# Sheet1.net
KiCad netlist of a schematic drawn in Altium Designer
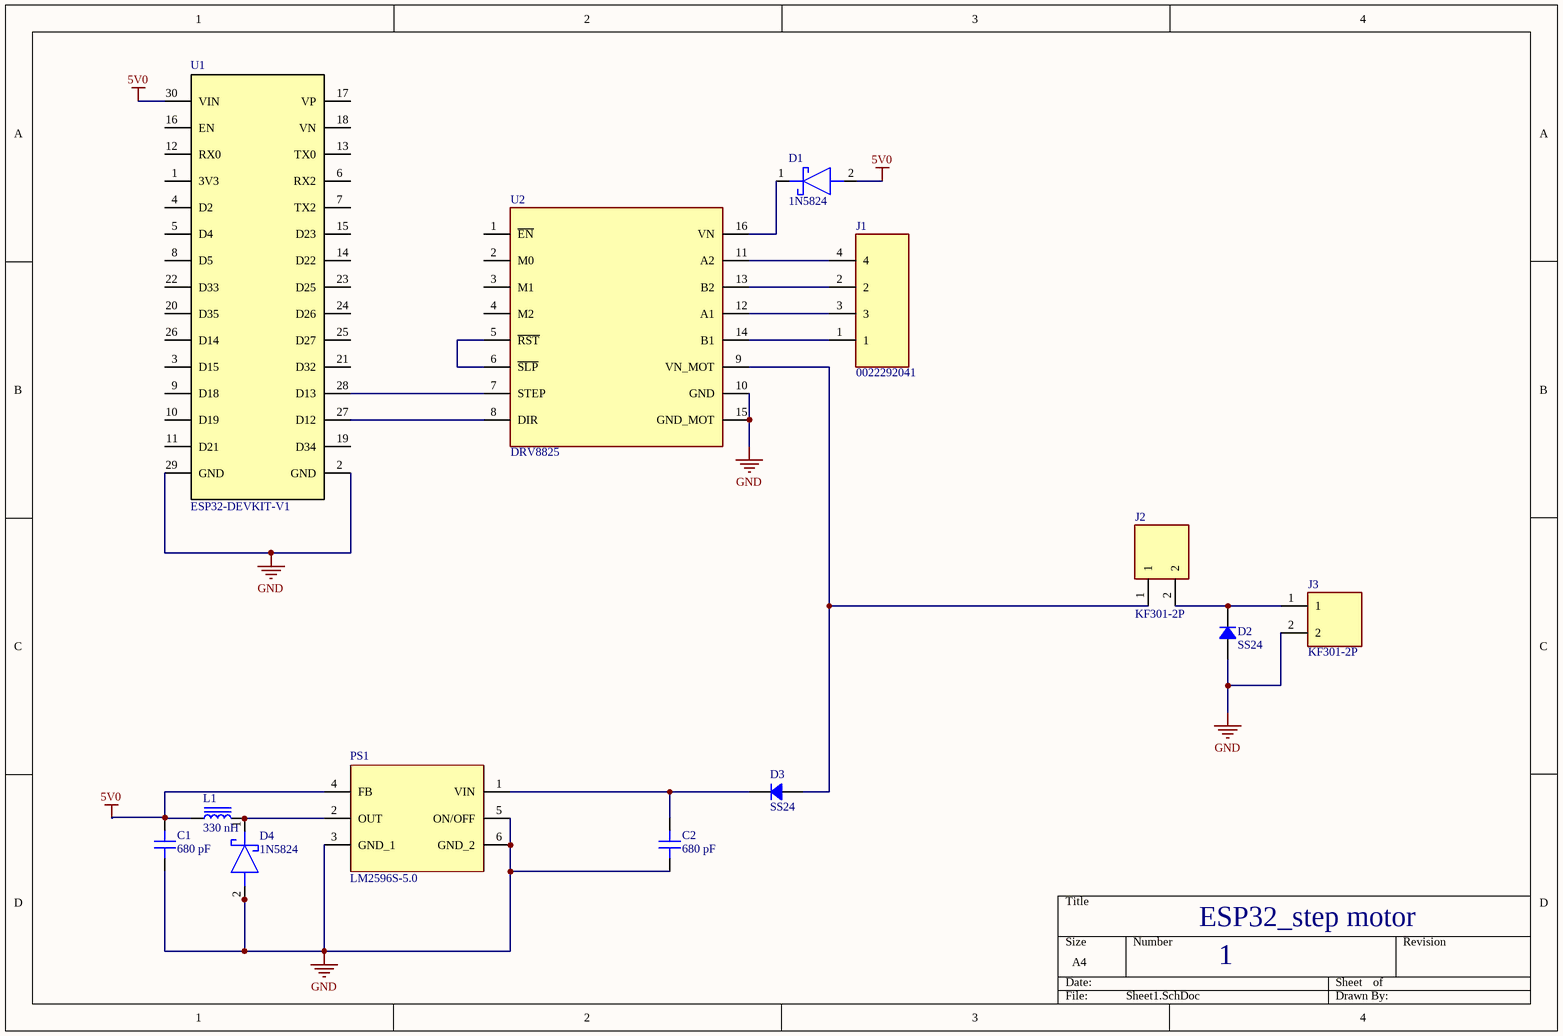
[diagram p0: Sheet1.SchDoc]

(export (version "E")
  (design (tool "Eeschema 10.0.6"))
  (components
    (comp (ref "C1")
      (value "680 pF")
      (footprint "CAP 0603_1608")
      (description "CAP CER 680PF 50V C0G/NPO 0603")
      (fields
        (field (name "PART NUMBER") "CC0603JRNPO9BN681")
        (field (name "CAPACITANCE") "680 pF")
        (field (name "MANUFACTURER") "Yageo")
      )
      (libsource (lib "Celestial Altium Library - altium_library") (part "Capacitor"))
    )
    (comp (ref "C2")
      (value "680 pF")
      (footprint "CAP 0603_1608")
      (description "CAP CER 680PF 50V C0G/NPO 0603")
      (fields
        (field (name "PART NUMBER") "CC0603JRNPO9BN681")
        (field (name "CAPACITANCE") "680 pF")
        (field (name "MANUFACTURER") "Yageo")
      )
      (libsource (lib "Celestial Altium Library - altium_library") (part "Capacitor"))
    )
    (comp (ref "D1")
      (value "1N5824")
      (footprint "DIOM5026X262N")
      (description "Schottky Diode")
      (fields (field (name "MOUSER PART NUMBER") "494-1N5824"))
      (libsource (lib "DRV8825_STEPPER_MOTOR_DRIVER_CARRIER") (part "1N5824"))
    )
    (comp (ref "D2")
      (value "SS24")
      (footprint "DO214AA SMB")
      (description "DIODE SCHOTTKY 40V 2A DO214AA")
      (fields (field (name "MANUFACTURER") "ON Semiconductor"))
      (libsource (lib "Celestial Altium Library - altium_library") (part "Diode"))
    )
    (comp (ref "D3")
      (value "SS24")
      (footprint "DO214AA SMB")
      (description "DIODE SCHOTTKY 40V 2A DO214AA")
      (fields (field (name "MANUFACTURER") "ON Semiconductor"))
      (libsource (lib "Celestial Altium Library - altium_library") (part "Diode"))
    )
    (comp (ref "D4")
      (value "1N5824")
      (footprint "DIOM5026X262N")
      (description "Schottky Diode")
      (fields (field (name "MOUSER PART NUMBER") "494-1N5824"))
      (libsource (lib "DRV8825_STEPPER_MOTOR_DRIVER_CARRIER") (part "1N5824"))
    )
    (comp (ref "J1")
      (value "0022292041")
      (footprint "0022292041")
      (description "Connector")
      (libsource (lib "ALL_IN_PJ") (part "0022292041"))
    )
    (comp (ref "J2")
      (value "KF301-2P")
      (footprint "HANDSON_KF301-2P")
      (description "2 Pin Terminal Block 5mm Pitch")
      (libsource (lib "") (part "KF301-2P_1"))
    )
    (comp (ref "J3")
      (value "KF301-2P")
      (footprint "HANDSON_KF301-2P")
      (description "2 Pin Terminal Block 5mm Pitch")
      (libsource (lib "ALL_IN_PJ") (part "KF301-2P"))
    )
    (comp (ref "L1")
      (value "330 nH")
      (footprint "BOURNS SRP5030T")
      (description "FIXED IND 330NH 14A 5 MOHM SMD")
      (fields (field (name "PART NUMBER") "SRP5030T-R33M") (field (name "MANUFACTURER") "Bourns Inc."))
      (libsource (lib "Celestial Altium Library - altium_library") (part "Inductor"))
    )
    (comp (ref "PS1")
      (value "LM2596S-5.0")
      (footprint "KTT0005B")
      (libsource (lib "DRV8825_STEPPER_MOTOR_DRIVER_CARRIER") (part "LM2596S-5.0"))
    )
    (comp (ref "U1")
      (value "ESP32-DEVKIT-V1")
      (footprint "MODULE_ESP32_DEVKIT_V1")
      (fields (field (name "MF") "Do it"))
      (libsource (lib "ALL_IN_PJ") (part "ESP32-DEVKIT-V1"))
    )
    (comp (ref "U2")
      (value "DRV8825")
      (footprint "IC_DRV8825_STEPPER_MOTOR_DRIVER_CARRIER")
      (description "Stepper motor controler; IC: DRV8825; 1.5A; Uin mot: 8.2Ã·45V")
      (fields (field (name "MP") "DRV8825_STEPPER_MOTOR_DRIVER_CARRIER"))
      (libsource (lib "DRV8825_STEPPER_MOTOR_DRIVER_CARRIER") (part "DRV8825_STEPPER_MOTOR_DRIVER_CARRIER"))
    )
  )
  (nets
    (net (code "1") (name "5V0") (class "Default")
      (node (ref "C1") (pin "2") (pinfunction "2_2") (pintype "passive"))
      (node (ref "D1") (pin "2") (pinfunction "A_2") (pintype "passive"))
      (node (ref "L1") (pin "1") (pinfunction "1_1") (pintype "passive"))
      (node (ref "PS1") (pin "4") (pinfunction "FB_4") (pintype "passive"))
      (node (ref "U1") (pin "30") (pinfunction "VIN_30") (pintype "passive"))
    )
    (net (code "2") (name "GND") (class "Default")
      (node (ref "C1") (pin "1") (pinfunction "1_1") (pintype "passive"))
      (node (ref "C2") (pin "1") (pinfunction "1_1") (pintype "passive"))
      (node (ref "D2") (pin "1") (pinfunction "1_1") (pintype "passive"))
      (node (ref "D4") (pin "2") (pinfunction "A_2") (pintype "passive"))
      (node (ref "J3") (pin "2") (pinfunction "2_2") (pintype "passive"))
      (node (ref "PS1") (pin "3") (pinfunction "GND_1_3") (pintype "passive"))
      (node (ref "PS1") (pin "5") (pinfunction "ON/OFF_5") (pintype "passive"))
      (node (ref "PS1") (pin "6") (pinfunction "GND_2_6") (pintype "passive"))
      (node (ref "U1") (pin "2") (pinfunction "GND_2") (pintype "passive"))
      (node (ref "U1") (pin "29") (pinfunction "GND_29") (pintype "passive"))
      (node (ref "U2") (pin "10") (pinfunction "GND_10") (pintype "passive"))
      (node (ref "U2") (pin "15") (pinfunction "GND_MOT_15") (pintype "power_in"))
    )
    (net (code "3") (name "Net-(D1-K)") (class "Default")
      (node (ref "D1") (pin "1") (pinfunction "K_1") (pintype "passive"))
      (node (ref "U2") (pin "16") (pinfunction "VN_16") (pintype "power_in"))
    )
    (net (code "4") (name "Net-(D2-Pad2)") (class "Default")
      (node (ref "D2") (pin "2") (pinfunction "2_2") (pintype "passive"))
      (node (ref "J2") (pin "2") (pinfunction "2_2") (pintype "passive"))
      (node (ref "J3") (pin "1") (pinfunction "1_1") (pintype "passive"))
    )
    (net (code "5") (name "Net-(D4-K)") (class "Default")
      (node (ref "D4") (pin "1") (pinfunction "K_1") (pintype "passive"))
      (node (ref "L1") (pin "2") (pinfunction "2_2") (pintype "passive"))
      (node (ref "PS1") (pin "2") (pinfunction "OUT_2") (pintype "passive"))
    )
    (net (code "6") (name "Net-(PS1-VIN)") (class "Default")
      (node (ref "C2") (pin "2") (pinfunction "2_2") (pintype "passive"))
      (node (ref "D3") (pin "2") (pinfunction "2_2") (pintype "passive"))
      (node (ref "PS1") (pin "1") (pinfunction "VIN_1") (pintype "passive"))
    )
    (net (code "7") (name "Net-(U1-D12)") (class "Default")
      (node (ref "U1") (pin "27") (pinfunction "D12_27") (pintype "passive"))
      (node (ref "U2") (pin "8") (pinfunction "DIR_8") (pintype "passive"))
    )
    (net (code "8") (name "Net-(U1-D13)") (class "Default")
      (node (ref "U1") (pin "28") (pinfunction "D13_28") (pintype "passive"))
      (node (ref "U2") (pin "7") (pinfunction "STEP_7") (pintype "passive"))
    )
    (net (code "9") (name "Net-(U2-A1)") (class "Default")
      (node (ref "J1") (pin "3") (pinfunction "3_3") (pintype "passive"))
      (node (ref "U2") (pin "12") (pinfunction "A1_12") (pintype "passive"))
    )
    (net (code "10") (name "Net-(U2-A2)") (class "Default")
      (node (ref "J1") (pin "4") (pinfunction "4_4") (pintype "passive"))
      (node (ref "U2") (pin "11") (pinfunction "A2_11") (pintype "passive"))
    )
    (net (code "11") (name "Net-(U2-B1)") (class "Default")
      (node (ref "J1") (pin "1") (pinfunction "1_1") (pintype "passive"))
      (node (ref "U2") (pin "14") (pinfunction "B1_14") (pintype "passive"))
    )
    (net (code "12") (name "Net-(U2-B2)") (class "Default")
      (node (ref "J1") (pin "2") (pinfunction "2_2") (pintype "passive"))
      (node (ref "U2") (pin "13") (pinfunction "B2_13") (pintype "passive"))
    )
    (net (code "13") (name "Net-(U2-VN_MOT)") (class "Default")
      (node (ref "D3") (pin "1") (pinfunction "1_1") (pintype "passive"))
      (node (ref "J2") (pin "1") (pinfunction "1_1") (pintype "passive"))
      (node (ref "U2") (pin "9") (pinfunction "VN_MOT_9") (pintype "power_in"))
    )
    (net (code "14") (name "Net-(U2-~{RST})") (class "Default")
      (node (ref "U2") (pin "5") (pinfunction "~{RST}_5") (pintype "passive"))
      (node (ref "U2") (pin "6") (pinfunction "~{SLP}_6") (pintype "passive"))
    )
    (net (code "15") (name "unconnected-(U1-3V3-Pad1)") (class "Default")
      (node (ref "U1") (pin "1") (pinfunction "3V3_1") (pintype "passive"))
    )
    (net (code "16") (name "unconnected-(U1-D2-Pad4)") (class "Default")
      (node (ref "U1") (pin "4") (pinfunction "D2_4") (pintype "passive"))
    )
    (net (code "17") (name "unconnected-(U1-D4-Pad5)") (class "Default")
      (node (ref "U1") (pin "5") (pinfunction "D4_5") (pintype "passive"))
    )
    (net (code "18") (name "unconnected-(U1-D5-Pad8)") (class "Default")
      (node (ref "U1") (pin "8") (pinfunction "D5_8") (pintype "passive"))
    )
    (net (code "19") (name "unconnected-(U1-D14-Pad26)") (class "Default")
      (node (ref "U1") (pin "26") (pinfunction "D14_26") (pintype "passive"))
    )
    (net (code "20") (name "unconnected-(U1-D15-Pad3)") (class "Default")
      (node (ref "U1") (pin "3") (pinfunction "D15_3") (pintype "passive"))
    )
    (net (code "21") (name "unconnected-(U1-D18-Pad9)") (class "Default")
      (node (ref "U1") (pin "9") (pinfunction "D18_9") (pintype "passive"))
    )
    (net (code "22") (name "unconnected-(U1-D19-Pad10)") (class "Default")
      (node (ref "U1") (pin "10") (pinfunction "D19_10") (pintype "passive"))
    )
    (net (code "23") (name "unconnected-(U1-D21-Pad11)") (class "Default")
      (node (ref "U1") (pin "11") (pinfunction "D21_11") (pintype "passive"))
    )
    (net (code "24") (name "unconnected-(U1-D22-Pad14)") (class "Default")
      (node (ref "U1") (pin "14") (pinfunction "D22_14") (pintype "passive"))
    )
    (net (code "25") (name "unconnected-(U1-D23-Pad15)") (class "Default")
      (node (ref "U1") (pin "15") (pinfunction "D23_15") (pintype "passive"))
    )
    (net (code "26") (name "unconnected-(U1-D25-Pad23)") (class "Default")
      (node (ref "U1") (pin "23") (pinfunction "D25_23") (pintype "passive"))
    )
    (net (code "27") (name "unconnected-(U1-D26-Pad24)") (class "Default")
      (node (ref "U1") (pin "24") (pinfunction "D26_24") (pintype "passive"))
    )
    (net (code "28") (name "unconnected-(U1-D27-Pad25)") (class "Default")
      (node (ref "U1") (pin "25") (pinfunction "D27_25") (pintype "passive"))
    )
    (net (code "29") (name "unconnected-(U1-D32-Pad21)") (class "Default")
      (node (ref "U1") (pin "21") (pinfunction "D32_21") (pintype "passive"))
    )
    (net (code "30") (name "unconnected-(U1-D33-Pad22)") (class "Default")
      (node (ref "U1") (pin "22") (pinfunction "D33_22") (pintype "passive"))
    )
    (net (code "31") (name "unconnected-(U1-D34-Pad19)") (class "Default")
      (node (ref "U1") (pin "19") (pinfunction "D34_19") (pintype "passive"))
    )
    (net (code "32") (name "unconnected-(U1-D35-Pad20)") (class "Default")
      (node (ref "U1") (pin "20") (pinfunction "D35_20") (pintype "passive"))
    )
    (net (code "33") (name "unconnected-(U1-EN-Pad16)") (class "Default")
      (node (ref "U1") (pin "16") (pinfunction "EN_16") (pintype "passive"))
    )
    (net (code "34") (name "unconnected-(U1-RX0-Pad12)") (class "Default")
      (node (ref "U1") (pin "12") (pinfunction "RX0_12") (pintype "passive"))
    )
    (net (code "35") (name "unconnected-(U1-RX2-Pad6)") (class "Default")
      (node (ref "U1") (pin "6") (pinfunction "RX2_6") (pintype "passive"))
    )
    (net (code "36") (name "unconnected-(U1-TX0-Pad13)") (class "Default")
      (node (ref "U1") (pin "13") (pinfunction "TX0_13") (pintype "passive"))
    )
    (net (code "37") (name "unconnected-(U1-TX2-Pad7)") (class "Default")
      (node (ref "U1") (pin "7") (pinfunction "TX2_7") (pintype "passive"))
    )
    (net (code "38") (name "unconnected-(U1-VN-Pad18)") (class "Default")
      (node (ref "U1") (pin "18") (pinfunction "VN_18") (pintype "passive"))
    )
    (net (code "39") (name "unconnected-(U1-VP-Pad17)") (class "Default")
      (node (ref "U1") (pin "17") (pinfunction "VP_17") (pintype "passive"))
    )
    (net (code "40") (name "unconnected-(U2-M0-Pad2)") (class "Default")
      (node (ref "U2") (pin "2") (pinfunction "M0_2") (pintype "passive"))
    )
    (net (code "41") (name "unconnected-(U2-M1-Pad3)") (class "Default")
      (node (ref "U2") (pin "3") (pinfunction "M1_3") (pintype "passive"))
    )
    (net (code "42") (name "unconnected-(U2-M2-Pad4)") (class "Default")
      (node (ref "U2") (pin "4") (pinfunction "M2_4") (pintype "passive"))
    )
    (net (code "43") (name "unconnected-(U2-~{EN}-Pad1)") (class "Default")
      (node (ref "U2") (pin "1") (pinfunction "~{EN}_1") (pintype "passive"))
    )
  )
)
